# Power.net
KiCad netlist of a schematic drawn in Altium Designer
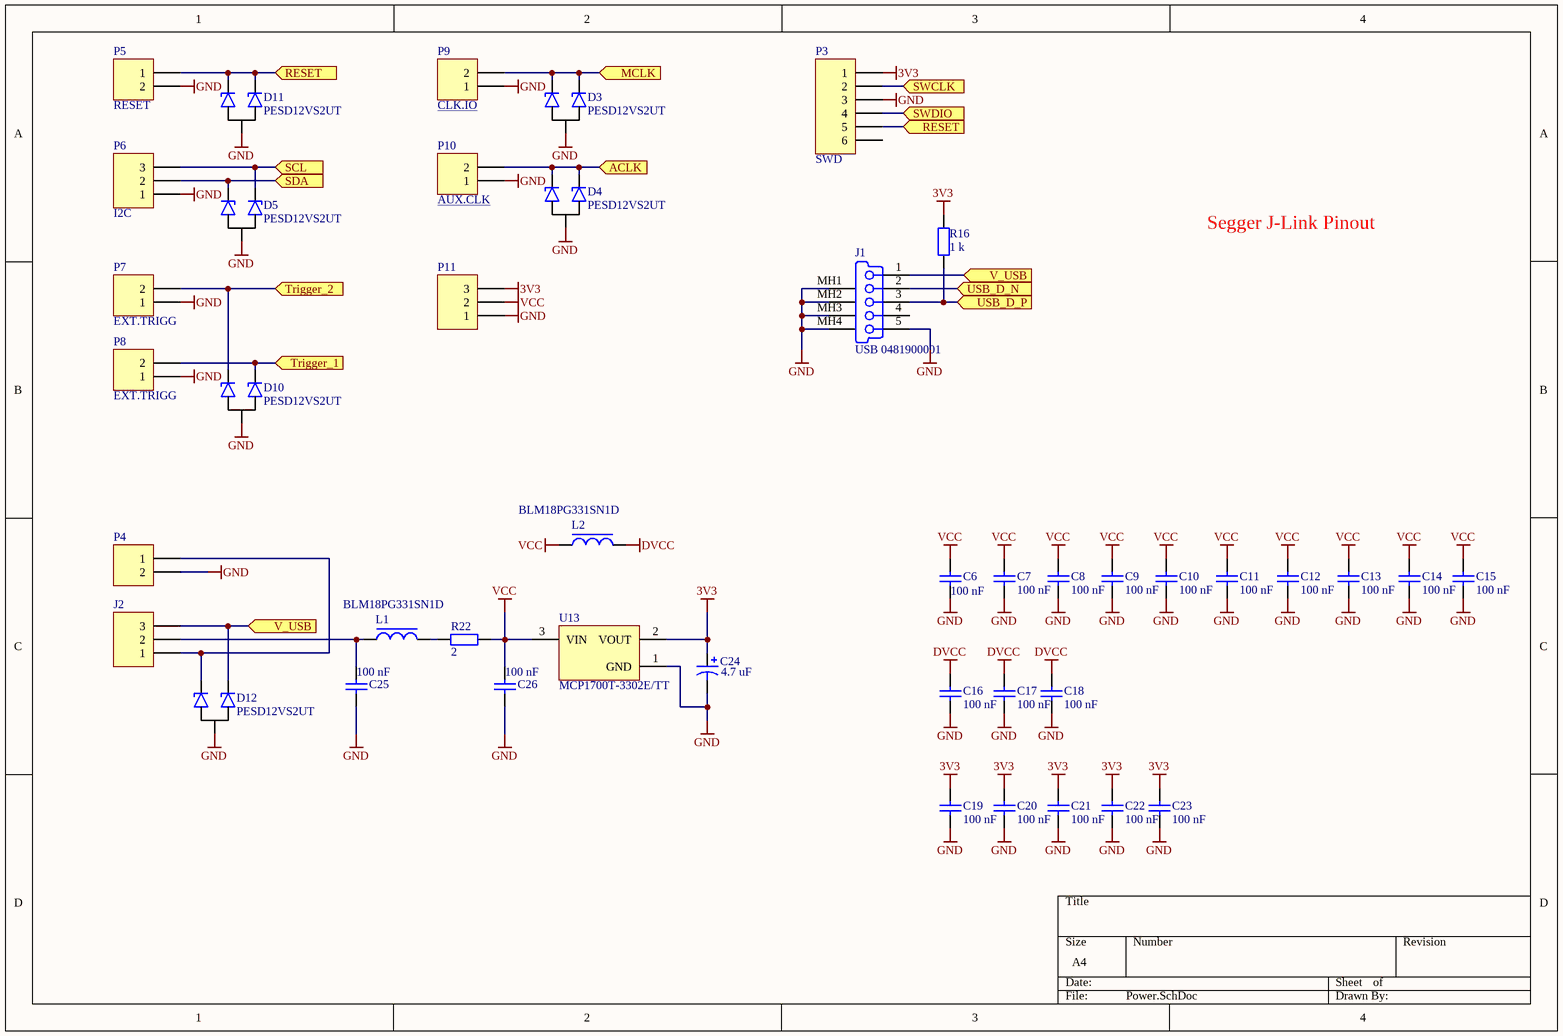
[diagram p0: Power.SchDoc]

(export (version "E")
  (design (tool "Eeschema 10.0.6"))
  (components
    (comp (ref "C6")
      (value "100 nF")
      (footprint "C1206")
      (description "Capacitor (Semiconductor SIM Model)")
      (fields (field (name "PUBLISHER") "Altium Limited"))
      (libsource (lib "Miscellaneous Devices") (part "Cap Semi"))
    )
    (comp (ref "C7")
      (value "100 nF")
      (footprint "C1206")
      (description "Capacitor (Semiconductor SIM Model)")
      (fields (field (name "PUBLISHER") "Altium Limited"))
      (libsource (lib "Miscellaneous Devices") (part "Cap Semi"))
    )
    (comp (ref "C8")
      (value "100 nF")
      (footprint "C1206")
      (description "Capacitor (Semiconductor SIM Model)")
      (fields (field (name "PUBLISHER") "Altium Limited"))
      (libsource (lib "Miscellaneous Devices") (part "Cap Semi"))
    )
    (comp (ref "C9")
      (value "100 nF")
      (footprint "C1206")
      (description "Capacitor (Semiconductor SIM Model)")
      (fields (field (name "PUBLISHER") "Altium Limited"))
      (libsource (lib "Miscellaneous Devices") (part "Cap Semi"))
    )
    (comp (ref "C10")
      (value "100 nF")
      (footprint "C1206")
      (description "Capacitor (Semiconductor SIM Model)")
      (fields (field (name "PUBLISHER") "Altium Limited"))
      (libsource (lib "Miscellaneous Devices") (part "Cap Semi"))
    )
    (comp (ref "C11")
      (value "100 nF")
      (footprint "C1206")
      (description "Capacitor (Semiconductor SIM Model)")
      (fields (field (name "PUBLISHER") "Altium Limited"))
      (libsource (lib "Miscellaneous Devices") (part "Cap Semi"))
    )
    (comp (ref "C12")
      (value "100 nF")
      (footprint "C1206")
      (description "Capacitor (Semiconductor SIM Model)")
      (fields (field (name "PUBLISHER") "Altium Limited"))
      (libsource (lib "Miscellaneous Devices") (part "Cap Semi"))
    )
    (comp (ref "C13")
      (value "100 nF")
      (footprint "C1206")
      (description "Capacitor (Semiconductor SIM Model)")
      (fields (field (name "PUBLISHER") "Altium Limited"))
      (libsource (lib "Miscellaneous Devices") (part "Cap Semi"))
    )
    (comp (ref "C14")
      (value "100 nF")
      (footprint "C1206")
      (description "Capacitor (Semiconductor SIM Model)")
      (fields (field (name "PUBLISHER") "Altium Limited"))
      (libsource (lib "Miscellaneous Devices") (part "Cap Semi"))
    )
    (comp (ref "C15")
      (value "100 nF")
      (footprint "C1206")
      (description "Capacitor (Semiconductor SIM Model)")
      (fields (field (name "PUBLISHER") "Altium Limited"))
      (libsource (lib "Miscellaneous Devices") (part "Cap Semi"))
    )
    (comp (ref "C16")
      (value "100 nF")
      (footprint "C1206")
      (description "Capacitor (Semiconductor SIM Model)")
      (fields (field (name "PUBLISHER") "Altium Limited"))
      (libsource (lib "Miscellaneous Devices") (part "Cap Semi"))
    )
    (comp (ref "C17")
      (value "100 nF")
      (footprint "C1206")
      (description "Capacitor (Semiconductor SIM Model)")
      (fields (field (name "PUBLISHER") "Altium Limited"))
      (libsource (lib "Miscellaneous Devices") (part "Cap Semi"))
    )
    (comp (ref "C18")
      (value "100 nF")
      (footprint "C1206")
      (description "Capacitor (Semiconductor SIM Model)")
      (fields (field (name "PUBLISHER") "Altium Limited"))
      (libsource (lib "Miscellaneous Devices") (part "Cap Semi"))
    )
    (comp (ref "C19")
      (value "100 nF")
      (footprint "C1206")
      (description "Capacitor (Semiconductor SIM Model)")
      (fields (field (name "PUBLISHER") "Altium Limited"))
      (libsource (lib "Miscellaneous Devices") (part "Cap Semi"))
    )
    (comp (ref "C20")
      (value "100 nF")
      (footprint "C1206")
      (description "Capacitor (Semiconductor SIM Model)")
      (fields (field (name "PUBLISHER") "Altium Limited"))
      (libsource (lib "Miscellaneous Devices") (part "Cap Semi"))
    )
    (comp (ref "C21")
      (value "100 nF")
      (footprint "C1206")
      (description "Capacitor (Semiconductor SIM Model)")
      (fields (field (name "PUBLISHER") "Altium Limited"))
      (libsource (lib "Miscellaneous Devices") (part "Cap Semi"))
    )
    (comp (ref "C22")
      (value "100 nF")
      (footprint "C1206")
      (description "Capacitor (Semiconductor SIM Model)")
      (fields (field (name "PUBLISHER") "Altium Limited"))
      (libsource (lib "Miscellaneous Devices") (part "Cap Semi"))
    )
    (comp (ref "C23")
      (value "100 nF")
      (footprint "C1206")
      (description "Capacitor (Semiconductor SIM Model)")
      (fields (field (name "PUBLISHER") "Altium Limited"))
      (libsource (lib "Miscellaneous Devices") (part "Cap Semi"))
    )
    (comp (ref "C24")
      (value "4.7 uF")
      (footprint "C1206")
      (description "Polarized Capacitor (Surface Mount)")
      (fields (field (name "PUBLISHER") "Altium Limited"))
      (libsource (lib "Miscellaneous Devices") (part "Cap Pol3"))
    )
    (comp (ref "C25")
      (value "100 nF")
      (footprint "C1206")
      (description "Capacitor (Semiconductor SIM Model)")
      (fields (field (name "PUBLISHER") "Altium Limited"))
      (libsource (lib "Miscellaneous Devices") (part "Cap Semi"))
    )
    (comp (ref "C26")
      (value "100 nF")
      (footprint "C1206")
      (description "Capacitor (Semiconductor SIM Model)")
      (fields (field (name "PUBLISHER") "Altium Limited"))
      (libsource (lib "Miscellaneous Devices") (part "Cap Semi"))
    )
    (comp (ref "D3")
      (value "PESD12VS2UT")
      (footprint "SOT-23")
      (description "Transil diod")
      (libsource (lib "Diody") (part "PESD5V2S2UT"))
    )
    (comp (ref "D4")
      (value "PESD12VS2UT")
      (footprint "SOT-23")
      (description "Transil diod")
      (libsource (lib "Diody") (part "PESD5V2S2UT"))
    )
    (comp (ref "D5")
      (value "PESD12VS2UT")
      (footprint "SOT-23")
      (description "Transil diod")
      (libsource (lib "Diody") (part "PESD5V2S2UT"))
    )
    (comp (ref "D10")
      (value "PESD12VS2UT")
      (footprint "SOT-23")
      (description "Transil diod")
      (libsource (lib "Diody") (part "PESD5V2S2UT"))
    )
    (comp (ref "D11")
      (value "PESD12VS2UT")
      (footprint "SOT-23")
      (description "Transil diod")
      (libsource (lib "Diody") (part "PESD5V2S2UT"))
    )
    (comp (ref "D12")
      (value "PESD12VS2UT")
      (footprint "SOT-23")
      (description "Transil diod")
      (libsource (lib "Diody") (part "PESD5V2S2UT"))
    )
    (comp (ref "J1")
      (value "USB 0481900001")
      (footprint "Mini USB-B")
      (libsource (lib "Connectors") (part "USB 0481900001"))
    )
    (comp (ref "J2")
      (value "Header 3")
      (footprint "Pin Header 1x3 TH Pitch 2.54mm")
      (description "Header, 3-Pin")
      (fields (field (name "PUBLISHER") "Altium Limited"))
      (libsource (lib "Miscellaneous Connectors") (part "Header 3"))
    )
    (comp (ref "L1")
      (value "BLM18PG331SN1D")
      (footprint "R1206")
      (description "Ferrit Bead")
      (libsource (lib "Coils") (part "BLM18PG331SN1D"))
    )
    (comp (ref "L2")
      (value "BLM18PG331SN1D")
      (footprint "R1206")
      (description "Ferrit Bead")
      (libsource (lib "Coils") (part "BLM18PG331SN1D"))
    )
    (comp (ref "P3")
      (value "SWD")
      (footprint "Pin Header 1x6 TH Pitch 2.54mm")
      (description "Header, 6-Pin")
      (fields (field (name "PUBLISHER") "Altium Limited"))
      (libsource (lib "Miscellaneous Connectors") (part "Header 6"))
    )
    (comp (ref "P4")
      (value "Header 2")
      (footprint "Pin Header 1x2 TH Pitch 2.54mm")
      (description "Header, 2-Pin")
      (fields (field (name "PUBLISHER") "Altium Limited"))
      (libsource (lib "Miscellaneous Connectors") (part "Header 2"))
    )
    (comp (ref "P5")
      (value "RESET")
      (footprint "Pin Header 1x2 TH Pitch 2.54mm")
      (description "Header, 2-Pin")
      (fields (field (name "PUBLISHER") "Altium Limited"))
      (libsource (lib "Miscellaneous Connectors") (part "Header 2"))
    )
    (comp (ref "P6")
      (value "I2C")
      (footprint "Pin Header 1x3 TH Pitch 2.54mm")
      (description "Header, 3-Pin")
      (fields (field (name "PUBLISHER") "Altium Limited"))
      (libsource (lib "Miscellaneous Connectors") (part "Header 3"))
    )
    (comp (ref "P7")
      (value "EXT.TRIGG")
      (footprint "Pin Header 1x2 TH Pitch 2.54mm")
      (description "Header, 2-Pin")
      (fields (field (name "PUBLISHER") "Altium Limited"))
      (libsource (lib "") (part "Header 2_1"))
    )
    (comp (ref "P8")
      (value "EXT.TRIGG")
      (footprint "Pin Header 1x2 TH Pitch 2.54mm")
      (description "Header, 2-Pin")
      (fields (field (name "PUBLISHER") "Altium Limited"))
      (libsource (lib "") (part "Header 2_1"))
    )
    (comp (ref "P9")
      (value "CLK.IO")
      (footprint "Pin Header 1x2 TH Pitch 2.54mm")
      (description "Header, 2-Pin")
      (fields (field (name "PUBLISHER") "Altium Limited"))
      (libsource (lib "") (part "Header 2_1"))
    )
    (comp (ref "P10")
      (value "AUX.CLK")
      (footprint "Pin Header 1x2 TH Pitch 2.54mm")
      (description "Header, 2-Pin")
      (fields (field (name "PUBLISHER") "Altium Limited"))
      (libsource (lib "") (part "Header 2_1"))
    )
    (comp (ref "P11")
      (value "Header 3")
      (footprint "Pin Header 1x3 TH Pitch 2.54mm")
      (description "Header, 3-Pin")
      (fields (field (name "PUBLISHER") "Altium Limited"))
      (libsource (lib "Miscellaneous Connectors") (part "Header 3"))
    )
    (comp (ref "R16")
      (value "1 k")
      (footprint "R1206")
      (description "Resistor")
      (fields (field (name "PUBLISHER") "Altium Limited"))
      (libsource (lib "") (part "Res2_1"))
    )
    (comp (ref "R22")
      (value "2")
      (footprint "R1206")
      (description "Resistor")
      (fields (field (name "PUBLISHER") "Altium Limited"))
      (libsource (lib "Miscellaneous Devices") (part "Res2"))
    )
    (comp (ref "U13")
      (value "MCP1700T-3302E/TT")
      (footprint "SOT-23_L")
      (description "Low Quiescent Current LDO, 3-Pin SOT-23, Extended Temperature, Tape and Reel")
      (fields (field (name "PUBLISHER") "Altium Limited"))
      (libsource (lib "Microchip Power Mgt Line Regulator") (part "MCP1700T-3302E/TT"))
    )
  )
  (nets
    (net (code "1") (name "/ACLK") (class "Default")
      (node (ref "D4") (pin "1") (pinfunction "1_1") (pintype "passive"))
      (node (ref "D4") (pin "2") (pinfunction "2_2") (pintype "passive"))
      (node (ref "P10") (pin "2") (pinfunction "2_2") (pintype "passive"))
    )
    (net (code "2") (name "/MCLK") (class "Default")
      (node (ref "D3") (pin "1") (pinfunction "1_1") (pintype "passive"))
      (node (ref "D3") (pin "2") (pinfunction "2_2") (pintype "passive"))
      (node (ref "P9") (pin "2") (pinfunction "2_2") (pintype "passive"))
    )
    (net (code "3") (name "/RESET") (class "Default")
      (node (ref "D11") (pin "1") (pinfunction "1_1") (pintype "passive"))
      (node (ref "D11") (pin "2") (pinfunction "2_2") (pintype "passive"))
      (node (ref "P3") (pin "5") (pinfunction "5_5") (pintype "passive"))
      (node (ref "P5") (pin "1") (pinfunction "1_1") (pintype "passive"))
    )
    (net (code "4") (name "/SCL") (class "Default")
      (node (ref "D5") (pin "2") (pinfunction "2_2") (pintype "passive"))
      (node (ref "P6") (pin "3") (pinfunction "3_3") (pintype "passive"))
    )
    (net (code "5") (name "/SDA") (class "Default")
      (node (ref "D5") (pin "1") (pinfunction "1_1") (pintype "passive"))
      (node (ref "P6") (pin "2") (pinfunction "2_2") (pintype "passive"))
    )
    (net (code "6") (name "/SWCLK") (class "Default")
      (node (ref "P3") (pin "2") (pinfunction "2_2") (pintype "passive"))
    )
    (net (code "7") (name "/SWDIO") (class "Default")
      (node (ref "P3") (pin "4") (pinfunction "4_4") (pintype "passive"))
    )
    (net (code "8") (name "/Trigger_1") (class "Default")
      (node (ref "D10") (pin "1") (pinfunction "1_1") (pintype "passive"))
      (node (ref "P8") (pin "2") (pinfunction "2_2") (pintype "passive"))
    )
    (net (code "9") (name "/Trigger_2") (class "Default")
      (node (ref "D10") (pin "2") (pinfunction "2_2") (pintype "passive"))
      (node (ref "P7") (pin "2") (pinfunction "2_2") (pintype "passive"))
    )
    (net (code "10") (name "/USB_D_N") (class "Default")
      (node (ref "J1") (pin "2") (pinfunction "D-_2") (pintype "passive"))
    )
    (net (code "11") (name "/USB_D_P") (class "Default")
      (node (ref "J1") (pin "3") (pinfunction "D+_3") (pintype "passive"))
      (node (ref "R16") (pin "1") (pinfunction "1_1") (pintype "passive"))
    )
    (net (code "12") (name "/V_USB") (class "Default")
      (node (ref "D12") (pin "1") (pinfunction "1_1") (pintype "passive"))
      (node (ref "J1") (pin "1") (pinfunction "V_BUS_(5V)_1") (pintype "passive"))
      (node (ref "J2") (pin "3") (pinfunction "3_3") (pintype "passive"))
    )
    (net (code "13") (name "3V3") (class "Default")
      (node (ref "C19") (pin "2") (pinfunction "2_2") (pintype "passive"))
      (node (ref "C20") (pin "2") (pinfunction "2_2") (pintype "passive"))
      (node (ref "C21") (pin "2") (pinfunction "2_2") (pintype "passive"))
      (node (ref "C22") (pin "2") (pinfunction "2_2") (pintype "passive"))
      (node (ref "C23") (pin "2") (pinfunction "2_2") (pintype "passive"))
      (node (ref "C24") (pin "1") (pinfunction "1_1") (pintype "passive"))
      (node (ref "P11") (pin "3") (pinfunction "3_3") (pintype "passive"))
      (node (ref "P3") (pin "1") (pinfunction "1_1") (pintype "passive"))
      (node (ref "R16") (pin "2") (pinfunction "2_2") (pintype "passive"))
      (node (ref "U13") (pin "2") (pinfunction "VOUT_2") (pintype "power_in"))
    )
    (net (code "14") (name "DVCC") (class "Default")
      (node (ref "C16") (pin "2") (pinfunction "2_2") (pintype "passive"))
      (node (ref "C17") (pin "2") (pinfunction "2_2") (pintype "passive"))
      (node (ref "C18") (pin "2") (pinfunction "2_2") (pintype "passive"))
      (node (ref "L2") (pin "2") (pinfunction "2_2") (pintype "passive"))
    )
    (net (code "15") (name "GND") (class "Default")
      (node (ref "C10") (pin "1") (pinfunction "1_1") (pintype "passive"))
      (node (ref "C11") (pin "1") (pinfunction "1_1") (pintype "passive"))
      (node (ref "C12") (pin "1") (pinfunction "1_1") (pintype "passive"))
      (node (ref "C13") (pin "1") (pinfunction "1_1") (pintype "passive"))
      (node (ref "C14") (pin "1") (pinfunction "1_1") (pintype "passive"))
      (node (ref "C15") (pin "1") (pinfunction "1_1") (pintype "passive"))
      (node (ref "C16") (pin "1") (pinfunction "1_1") (pintype "passive"))
      (node (ref "C17") (pin "1") (pinfunction "1_1") (pintype "passive"))
      (node (ref "C18") (pin "1") (pinfunction "1_1") (pintype "passive"))
      (node (ref "C19") (pin "1") (pinfunction "1_1") (pintype "passive"))
      (node (ref "C20") (pin "1") (pinfunction "1_1") (pintype "passive"))
      (node (ref "C21") (pin "1") (pinfunction "1_1") (pintype "passive"))
      (node (ref "C22") (pin "1") (pinfunction "1_1") (pintype "passive"))
      (node (ref "C23") (pin "1") (pinfunction "1_1") (pintype "passive"))
      (node (ref "C24") (pin "2") (pinfunction "2_2") (pintype "passive"))
      (node (ref "C25") (pin "2") (pinfunction "2_2") (pintype "passive"))
      (node (ref "C26") (pin "2") (pinfunction "2_2") (pintype "passive"))
      (node (ref "C6") (pin "1") (pinfunction "1_1") (pintype "passive"))
      (node (ref "C7") (pin "1") (pinfunction "1_1") (pintype "passive"))
      (node (ref "C8") (pin "1") (pinfunction "1_1") (pintype "passive"))
      (node (ref "C9") (pin "1") (pinfunction "1_1") (pintype "passive"))
      (node (ref "D10") (pin "3") (pinfunction "3_3") (pintype "passive"))
      (node (ref "D11") (pin "3") (pinfunction "3_3") (pintype "passive"))
      (node (ref "D12") (pin "3") (pinfunction "3_3") (pintype "passive"))
      (node (ref "D3") (pin "3") (pinfunction "3_3") (pintype "passive"))
      (node (ref "D4") (pin "3") (pinfunction "3_3") (pintype "passive"))
      (node (ref "D5") (pin "3") (pinfunction "3_3") (pintype "passive"))
      (node (ref "J1") (pin "5") (pinfunction "GND_5") (pintype "passive"))
      (node (ref "J1") (pin "MH1") (pinfunction "Tab_MH1") (pintype "passive"))
      (node (ref "J1") (pin "MH2") (pinfunction "Tab_MH2") (pintype "passive"))
      (node (ref "J1") (pin "MH3") (pinfunction "Tab_MH3") (pintype "passive"))
      (node (ref "J1") (pin "MH4") (pinfunction "Tab_MH4") (pintype "passive"))
      (node (ref "P10") (pin "1") (pinfunction "1_1") (pintype "passive"))
      (node (ref "P11") (pin "1") (pinfunction "1_1") (pintype "passive"))
      (node (ref "P3") (pin "3") (pinfunction "3_3") (pintype "passive"))
      (node (ref "P4") (pin "2") (pinfunction "2_2") (pintype "passive"))
      (node (ref "P5") (pin "2") (pinfunction "2_2") (pintype "passive"))
      (node (ref "P6") (pin "1") (pinfunction "1_1") (pintype "passive"))
      (node (ref "P7") (pin "1") (pinfunction "1_1") (pintype "passive"))
      (node (ref "P8") (pin "1") (pinfunction "1_1") (pintype "passive"))
      (node (ref "P9") (pin "1") (pinfunction "1_1") (pintype "passive"))
      (node (ref "U13") (pin "1") (pinfunction "GND_1") (pintype "power_in"))
    )
    (net (code "16") (name "Net-(C25-Pad1)") (class "Default")
      (node (ref "C25") (pin "1") (pinfunction "1_1") (pintype "passive"))
      (node (ref "J2") (pin "2") (pinfunction "2_2") (pintype "passive"))
      (node (ref "L1") (pin "1") (pinfunction "1_1") (pintype "passive"))
    )
    (net (code "17") (name "Net-(D12-Pad2)") (class "Default")
      (node (ref "D12") (pin "2") (pinfunction "2_2") (pintype "passive"))
      (node (ref "J2") (pin "1") (pinfunction "1_1") (pintype "passive"))
      (node (ref "P4") (pin "1") (pinfunction "1_1") (pintype "passive"))
    )
    (net (code "18") (name "Net-(L1-Pad2)") (class "Default")
      (node (ref "L1") (pin "2") (pinfunction "2_2") (pintype "passive"))
      (node (ref "R22") (pin "2") (pinfunction "2_2") (pintype "passive"))
    )
    (net (code "19") (name "VCC") (class "Default")
      (node (ref "C10") (pin "2") (pinfunction "2_2") (pintype "passive"))
      (node (ref "C11") (pin "2") (pinfunction "2_2") (pintype "passive"))
      (node (ref "C12") (pin "2") (pinfunction "2_2") (pintype "passive"))
      (node (ref "C13") (pin "2") (pinfunction "2_2") (pintype "passive"))
      (node (ref "C14") (pin "2") (pinfunction "2_2") (pintype "passive"))
      (node (ref "C15") (pin "2") (pinfunction "2_2") (pintype "passive"))
      (node (ref "C26") (pin "1") (pinfunction "1_1") (pintype "passive"))
      (node (ref "C6") (pin "2") (pinfunction "2_2") (pintype "passive"))
      (node (ref "C7") (pin "2") (pinfunction "2_2") (pintype "passive"))
      (node (ref "C8") (pin "2") (pinfunction "2_2") (pintype "passive"))
      (node (ref "C9") (pin "2") (pinfunction "2_2") (pintype "passive"))
      (node (ref "L2") (pin "1") (pinfunction "1_1") (pintype "passive"))
      (node (ref "P11") (pin "2") (pinfunction "2_2") (pintype "passive"))
      (node (ref "R22") (pin "1") (pinfunction "1_1") (pintype "passive"))
      (node (ref "U13") (pin "3") (pinfunction "VIN_3") (pintype "power_in"))
    )
    (net (code "20") (name "unconnected-(J1-NC-Pad4)") (class "Default")
      (node (ref "J1") (pin "4") (pinfunction "NC_4") (pintype "passive"))
    )
    (net (code "21") (name "unconnected-(P3-Pad6)") (class "Default")
      (node (ref "P3") (pin "6") (pinfunction "6_6") (pintype "passive"))
    )
  )
)
